# Thande.net
KiCad netlist of a schematic drawn in Altium Designer
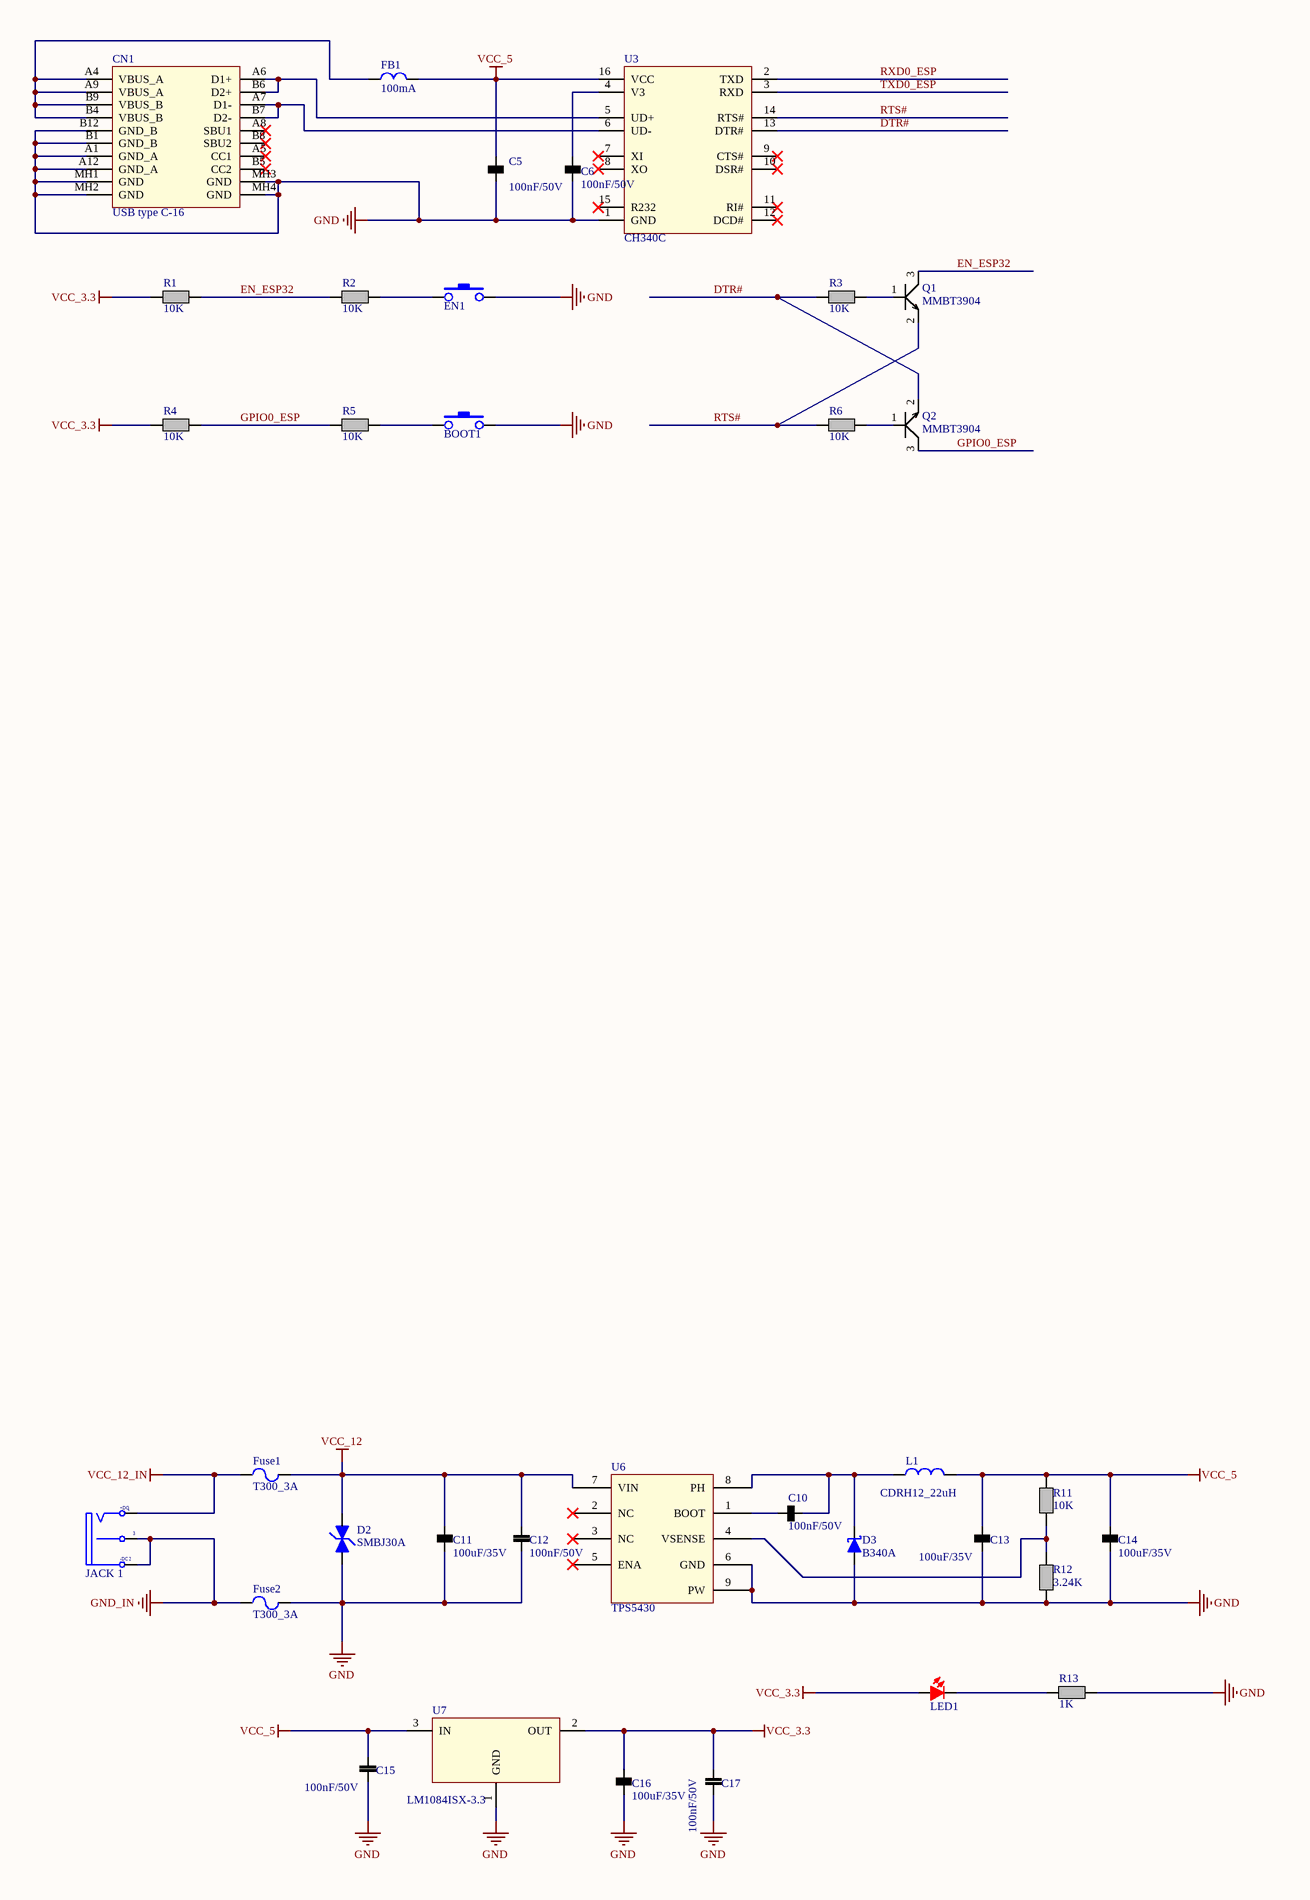
[diagram p0: Thande.SchDoc, left]
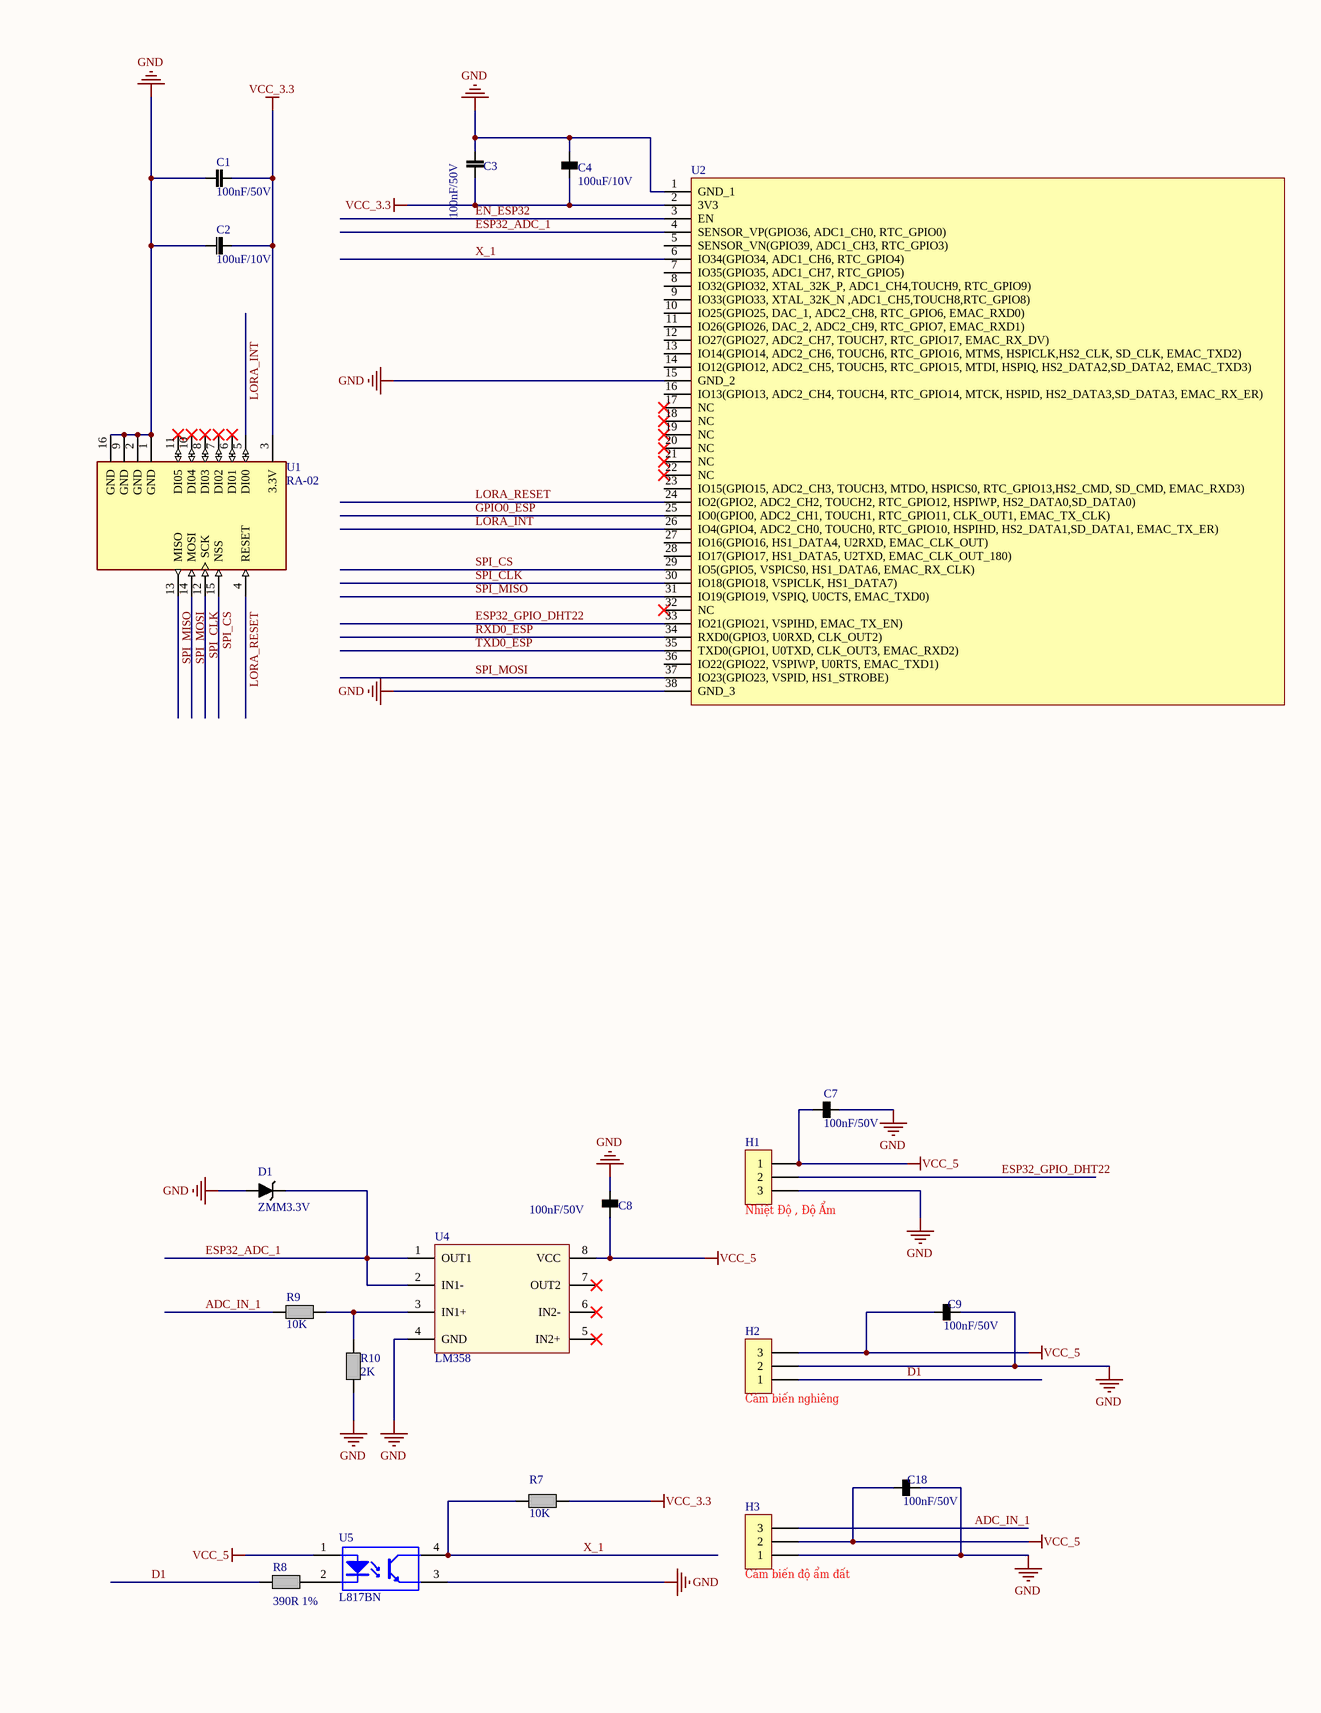
[diagram p1: Thande.SchDoc, right]

(export (version "E")
  (design (tool "Eeschema 10.0.6"))
  (components
    (comp (ref "BOOT1")
      (value "SW_2pin_SMD")
      (footprint "SW2-SMD**")
      (libsource (lib "Milky_Way") (part "SW_2pin_SMD"))
    )
    (comp (ref "C1")
      (value "100nF/50V")
      (footprint "CAP-0805**")
      (description "2Pin-SMD-0805 ,Ceramic X7R")
      (libsource (lib "Milky_Way") (part "Cap-100nF/50V_0805"))
    )
    (comp (ref "C2")
      (value "100uF/10V")
      (footprint "CAP-TANTA-3528**")
      (description "Cap-Tantalum  SMD3528 3.5mm x 2.8mm")
      (libsource (lib "Milky_Way") (part "Cap-Tanta_100uF/10V 3528"))
    )
    (comp (ref "C3")
      (value "100nF/50V")
      (footprint "CAP-0805**")
      (description "2Pin-SMD-0805 ,Ceramic X7R")
      (libsource (lib "Milky_Way") (part "Cap-100nF/50V_0805"))
    )
    (comp (ref "C4")
      (value "100uF/10V")
      (footprint "CAP-TANTA-3528**")
      (description "Cap-Tantalum  SMD3528 3.5mm x 2.8mm")
      (libsource (lib "") (part "Cap-Tanta_100uF/10V 3528_1"))
    )
    (comp (ref "C5")
      (value "100nF/50V")
      (footprint "CAP-0805**")
      (description "2Pin-SMD-0805 ,Ceramic X7R")
      (libsource (lib "Milky_Way") (part "Cap-100nF/50V_0805"))
    )
    (comp (ref "C6")
      (value "100nF/50V")
      (footprint "CAP-0805**")
      (description "2Pin-SMD-0805 ,Ceramic X7R")
      (libsource (lib "Milky_Way") (part "Cap-100nF/50V_0805"))
    )
    (comp (ref "C7")
      (value "100nF/50V")
      (footprint "CAP-0805**")
      (description "2Pin-SMD-0805 ,Ceramic X7R")
      (libsource (lib "Milky_Way") (part "Cap-100nF/50V_0805"))
    )
    (comp (ref "C8")
      (value "100nF/50V")
      (footprint "CAP-0805**")
      (description "2Pin-SMD-0805 ,Ceramic X7R")
      (libsource (lib "Milky_Way") (part "Cap-100nF/50V_0805"))
    )
    (comp (ref "C9")
      (value "100nF/50V")
      (footprint "CAP-0805**")
      (description "2Pin-SMD-0805 ,Ceramic X7R")
      (libsource (lib "Milky_Way") (part "Cap-100nF/50V_0805"))
    )
    (comp (ref "C10")
      (value "100nF/50V")
      (footprint "CAP-0805**")
      (description "2Pin-SMD-0805 ,Ceramic X7R")
      (libsource (lib "Milky_Way") (part "Cap-100nF/50V_0805"))
    )
    (comp (ref "C11")
      (value "100uF/35V")
      (footprint "CAP-AL- Size D8_6.3×7.7 mm**")
      (description "Cap-Al-Size D8_6.3×7.7 mm")
      (libsource (lib "Milky_Way") (part "Cap-Al_100uF/35V"))
    )
    (comp (ref "C12")
      (value "100nF/50V")
      (footprint "CAP-0805**")
      (description "2Pin-SMD-0805 ,Ceramic X7R")
      (libsource (lib "Milky_Way") (part "Cap-100nF/50V_0805"))
    )
    (comp (ref "C13")
      (value "100uF/35V")
      (footprint "CAP-AL- Size D8_6.3×7.7 mm**")
      (description "Cap-Al-Size D8_6.3×7.7 mm")
      (libsource (lib "Milky_Way") (part "Cap-Al_100uF/35V"))
    )
    (comp (ref "C14")
      (value "100uF/35V")
      (footprint "CAP-AL- Size D8_6.3×7.7 mm**")
      (description "Cap-Al-Size D8_6.3×7.7 mm")
      (libsource (lib "Milky_Way") (part "Cap-Al_100uF/35V"))
    )
    (comp (ref "C15")
      (value "100nF/50V")
      (footprint "CAP-0805**")
      (description "2Pin-SMD-0805 ,Ceramic X7R")
      (libsource (lib "Milky_Way") (part "Cap-100nF/50V_0805"))
    )
    (comp (ref "C16")
      (value "100uF/35V")
      (footprint "CAP-AL- Size D8_6.3×7.7 mm**")
      (description "Cap-Al-Size D8_6.3×7.7 mm")
      (libsource (lib "Milky_Way") (part "Cap-Al_100uF/35V"))
    )
    (comp (ref "C17")
      (value "100nF/50V")
      (footprint "CAP-0805**")
      (description "2Pin-SMD-0805 ,Ceramic X7R")
      (libsource (lib "Milky_Way") (part "Cap-100nF/50V_0805"))
    )
    (comp (ref "C18")
      (value "100nF/50V")
      (footprint "CAP-0805**")
      (description "2Pin-SMD-0805 ,Ceramic X7R")
      (libsource (lib "Milky_Way") (part "Cap-100nF/50V_0805"))
    )
    (comp (ref "CN1")
      (value "USB type C-16")
      (footprint "USB TYPE C-16**")
      (fields (field (name "MF") "Valcon") (field (name "MP") "CSP-USC16-TR"))
      (libsource (lib "Milky_Way") (part "USB type C-16"))
    )
    (comp (ref "D1")
      (value "ZMM3.3V")
      (footprint "DIO_SOD-80C**")
      (description "DZener_ZMM3.3V,SOD-80C")
      (libsource (lib "Milky_Way") (part "DZener_ZMM3.3V"))
    )
    (comp (ref "D2")
      (value "SMBJ30A")
      (footprint "DO-214AA**")
      (description "DO-214AA**")
      (libsource (lib "Milky_Way") (part "D-TVS_SMBJ30A"))
    )
    (comp (ref "D3")
      (value "B340A")
      (footprint "DO-214AC**")
      (description "DO_214AC")
      (fields (field (name "PUBLISHER") "Altium Limited"))
      (libsource (lib "Milky_Way") (part "DSchottky_B340A"))
    )
    (comp (ref "EN1")
      (value "SW_2pin_SMD")
      (footprint "SW2-SMD**")
      (libsource (lib "Milky_Way") (part "SW_2pin_SMD"))
    )
    (comp (ref "FB1")
      (value "100mA")
      (footprint "FB 0805**")
      (description "FB0805/600R/0805")
      (fields (field (name "PUBLISHER") "Altium Limited"))
      (libsource (lib "Milky_Way") (part "FB0805/600R_0805"))
    )
    (comp (ref "Fuse1")
      (value "T300_3A")
      (footprint "FUSE-1812**")
      (description "SMD 1812")
      (libsource (lib "Milky_Way") (part "FUSE 3A _1812"))
    )
    (comp (ref "Fuse2")
      (value "T300_3A")
      (footprint "FUSE-1812**")
      (description "SMD 1812")
      (libsource (lib "Milky_Way") (part "FUSE 3A _1812"))
    )
    (comp (ref "H1")
      (value "Header 3P 2.54 Duc Thang")
      (footprint "XH2.54M-3")
      (description "Cắm")
      (libsource (lib "") (part "Header 3P 2.54 Duc Thang_1"))
    )
    (comp (ref "H2")
      (value "Header 3P 2.54 Duc Thang")
      (footprint "XH2.54M-3")
      (description "Cắm")
      (libsource (lib "Altium_Lib_by_KhueNguyenCreator") (part "Header 3P 2.54 Duc Thang"))
    )
    (comp (ref "H3")
      (value "Header 3P 2.54 Duc Thang")
      (footprint "XH2.54M-3")
      (description "Cắm")
      (libsource (lib "Altium_Lib_by_KhueNguyenCreator") (part "Header 3P 2.54 Duc Thang"))
    )
    (comp (ref "JACK 1")
      (value "DC3501")
      (footprint "DC_005**")
      (description "Jack DC3.5x1.3MM DC3501")
      (libsource (lib "Milky_Way") (part "Jack  DC3501"))
    )
    (comp (ref "L1")
      (value "CDRH12_22uH")
      (footprint "IND_CDRH12_12x12x7MM**")
      (description "CDRH12_12x12x7MM**")
      (fields
        (field (name "MANUFACTURER") "Generic Components")
        (field (name "PUBLISHER") "Altium Hobart Technology Centre")
      )
      (libsource (lib "Milky_Way") (part "IN_CDRH12_22uH"))
    )
    (comp (ref "LED1")
      (value "LedRed")
      (footprint "LED-0805-Red**")
      (description "2Pin-SMD")
      (libsource (lib "Milky_Way") (part "LedRed"))
    )
    (comp (ref "Q1")
      (value "MMBT3904")
      (footprint "SOT23-3 **")
      (description "3PIN-SOT23,MMBT3904")
      (libsource (lib "Milky_Way") (part "TRA-N_MMBT3904"))
    )
    (comp (ref "Q2")
      (value "MMBT3904")
      (footprint "SOT23-3 **")
      (description "3PIN-SOT23,MMBT3904")
      (libsource (lib "Milky_Way") (part "TRA-N_MMBT3904"))
    )
    (comp (ref "R1")
      (value "10K")
      (footprint "Res-0805**")
      (description "Res-10K 0805 SMD")
      (libsource (lib "Milky_Way") (part "Res-10K 0805 SMD"))
    )
    (comp (ref "R2")
      (value "10K")
      (footprint "Res-0805**")
      (description "Res-10K 0805 SMD")
      (libsource (lib "Milky_Way") (part "Res-10K 0805 SMD"))
    )
    (comp (ref "R3")
      (value "10K")
      (footprint "Res-0805**")
      (description "Res-10K 0805 SMD")
      (libsource (lib "Milky_Way") (part "Res-10K 0805 SMD"))
    )
    (comp (ref "R4")
      (value "10K")
      (footprint "Res-0805**")
      (description "Res-10K 0805 SMD")
      (libsource (lib "Milky_Way") (part "Res-10K 0805 SMD"))
    )
    (comp (ref "R5")
      (value "10K")
      (footprint "Res-0805**")
      (description "Res-10K 0805 SMD")
      (libsource (lib "Milky_Way") (part "Res-10K 0805 SMD"))
    )
    (comp (ref "R6")
      (value "10K")
      (footprint "Res-0805**")
      (description "Res-10K 0805 SMD")
      (libsource (lib "Milky_Way") (part "Res-10K 0805 SMD"))
    )
    (comp (ref "R7")
      (value "10K")
      (footprint "Res-0805**")
      (description "Res-10K 0805 SMD")
      (libsource (lib "Milky_Way") (part "Res-10K 0805 SMD"))
    )
    (comp (ref "R8")
      (value "390R 1%")
      (footprint "Res-0805**")
      (libsource (lib "Milky_Way") (part "Res-390R 1% 0805 SMD"))
    )
    (comp (ref "R9")
      (value "10K")
      (footprint "Res-0805**")
      (description "Res-10K 0805 SMD")
      (libsource (lib "Milky_Way") (part "Res-10K 0805 SMD"))
    )
    (comp (ref "R10")
      (value "2K")
      (footprint "Res-0805**")
      (description "Res-2KK 0805 SMD")
      (libsource (lib "Milky_Way") (part "Res-2K 0805 SMD"))
    )
    (comp (ref "R11")
      (value "10K")
      (footprint "Res-0805**")
      (description "Res-10K 0805 SMD")
      (libsource (lib "Milky_Way") (part "Res-10K 0805 SMD"))
    )
    (comp (ref "R12")
      (value "3.24K")
      (footprint "Res-0805**")
      (description "Res-3.24K 0805 SMD")
      (libsource (lib "Milky_Way") (part "Res-3.24K 0805 SMD"))
    )
    (comp (ref "R13")
      (value "1K")
      (footprint "Res-0805**")
      (description "Res-1K 0805 SMD")
      (libsource (lib "Milky_Way") (part "Res-1K 0805 SMD"))
    )
    (comp (ref "U1")
      (value "RA-02")
      (footprint "RA-02")
      (fields (field (name "MF") "Ai-Thinker"))
      (libsource (lib "RA-02") (part "RA-02"))
    )
    (comp (ref "U2")
      (value "~")
      (footprint "ESP32WROOM32E8MB")
      (description "Integrated Circuit")
      (fields
        (field (name "MANUFACTURER_PART_NUMBER") "ESP32-WROOM-32E (8MB)")
        (field (name "MOUSER PART NUMBER") "356-ESP32WRM32E164PH")
      )
      (libsource (lib "ThuVienDoAn") (part "ESP32-WROOM-32E__8MB_"))
    )
    (comp (ref "U3")
      (value "CH340C")
      (footprint "SOIC-16**")
      (description "16Pin-SOIC")
      (libsource (lib "Milky_Way") (part "CH340C"))
    )
    (comp (ref "U4")
      (value "LM358")
      (footprint "SOIC8**")
      (description "SOIC8")
      (libsource (lib "Milky_Way") (part "LM358"))
    )
    (comp (ref "U5")
      (value "L817BN")
      (footprint "SOP-4**")
      (description "L817BN SOP4")
      (libsource (lib "Milky_Way") (part "OPTO_L817BN"))
    )
    (comp (ref "U6")
      (value "TPS5430")
      (footprint "SOIC8-PAD**")
      (description "SOIC8 pad-Height 1.7mm")
      (libsource (lib "Milky_Way") (part "TPS5430"))
    )
    (comp (ref "U7")
      (value "LM1084ISX-3.3")
      (footprint "TO-263/D2PAK")
      (description "TO263-3")
      (libsource (lib "Milky_Way") (part "LM1084ISX-3.3"))
    )
  )
  (nets
    (net (code "2") (name "/ADC_IN_1") (class "Default")
      (node (ref "H3") (pin "3") (pinfunction "3_3") (pintype "passive"))
      (node (ref "R9") (pin "2") (pinfunction "2_2") (pintype "passive"))
    )
    (net (code "3") (name "/D1") (class "Default")
      (node (ref "H2") (pin "1") (pinfunction "1_1") (pintype "passive"))
      (node (ref "R8") (pin "1") (pinfunction "1_1") (pintype "passive"))
    )
    (net (code "4") (name "/DTR#") (class "Default")
      (node (ref "Q2") (pin "2") (pinfunction "2_2") (pintype "passive"))
      (node (ref "R3") (pin "2") (pinfunction "2_2") (pintype "passive"))
      (node (ref "U3") (pin "13") (pinfunction "DTR#_13") (pintype "passive"))
    )
    (net (code "5") (name "/EN_ESP32") (class "Default")
      (node (ref "Q1") (pin "3") (pinfunction "3_3") (pintype "passive"))
      (node (ref "R1") (pin "1") (pinfunction "1_1") (pintype "passive"))
      (node (ref "R2") (pin "2") (pinfunction "2_2") (pintype "passive"))
      (node (ref "U2") (pin "3") (pinfunction "EN_3") (pintype "passive"))
    )
    (net (code "6") (name "/ESP32_ADC_1") (class "Default")
      (node (ref "D1") (pin "2") (pinfunction "K_2") (pintype "passive"))
      (node (ref "U2") (pin "4") (pinfunction "SENSOR_VP(GPIO36,_ADC1_CH0,_RTC_GPIO0)_4") (pintype "passive"))
      (node (ref "U4") (pin "1") (pinfunction "OUT1_1") (pintype "passive"))
      (node (ref "U4") (pin "2") (pinfunction "IN1-_2") (pintype "passive"))
    )
    (net (code "7") (name "/ESP32_GPIO_DHT22") (class "Default")
      (node (ref "H1") (pin "2") (pinfunction "2_2") (pintype "passive"))
      (node (ref "U2") (pin "33") (pinfunction "IO21(GPIO21,_VSPIHD,_EMAC_TX_EN)_33") (pintype "passive"))
    )
    (net (code "8") (name "/GPIO0_ESP") (class "Default")
      (node (ref "Q2") (pin "3") (pinfunction "3_3") (pintype "passive"))
      (node (ref "R4") (pin "1") (pinfunction "1_1") (pintype "passive"))
      (node (ref "R5") (pin "2") (pinfunction "2_2") (pintype "passive"))
      (node (ref "U2") (pin "25") (pinfunction "IO0(GPIO0,_ADC2_CH1,_TOUCH1,_RTC_GPIO11,_CLK_OUT1,_EMAC_TX_CLK)_25") (pintype "passive"))
    )
    (net (code "9") (name "/LORA_INT") (class "Default")
      (node (ref "U1") (pin "5") (pinfunction "DI00_5") (pintype "bidirectional"))
      (node (ref "U2") (pin "26") (pinfunction "IO4(GPIO4,_ADC2_CH0,_TOUCH0,_RTC_GPIO10,_HSPIHD,_HS2_DATA1,SD_DATA1,_EMAC_TX_ER)_26") (pintype "passive"))
    )
    (net (code "10") (name "/LORA_RESET") (class "Default")
      (node (ref "U1") (pin "4") (pinfunction "RESET_4") (pintype "input"))
      (node (ref "U2") (pin "24") (pinfunction "IO2(GPIO2,_ADC2_CH2,_TOUCH2,_RTC_GPIO12,_HSPIWP,_HS2_DATA0,SD_DATA0)_24") (pintype "passive"))
    )
    (net (code "11") (name "/RTS#") (class "Default")
      (node (ref "Q1") (pin "2") (pinfunction "2_2") (pintype "passive"))
      (node (ref "R6") (pin "2") (pinfunction "2_2") (pintype "passive"))
      (node (ref "U3") (pin "14") (pinfunction "RTS#_14") (pintype "passive"))
    )
    (net (code "12") (name "/RXD0_ESP") (class "Default")
      (node (ref "U2") (pin "34") (pinfunction "RXD0(GPIO3,_U0RXD,_CLK_OUT2)_34") (pintype "passive"))
      (node (ref "U3") (pin "2") (pinfunction "TXD_2") (pintype "passive"))
    )
    (net (code "13") (name "/SPI_CLK") (class "Default")
      (node (ref "U1") (pin "12") (pinfunction "SCK_12") (pintype "input"))
      (node (ref "U2") (pin "30") (pinfunction "IO18(GPIO18,_VSPICLK,_HS1_DATA7)_30") (pintype "passive"))
    )
    (net (code "14") (name "/SPI_CS") (class "Default")
      (node (ref "U1") (pin "15") (pinfunction "NSS_15") (pintype "input"))
      (node (ref "U2") (pin "29") (pinfunction "IO5(GPIO5,_VSPICS0,_HS1_DATA6,_EMAC_RX_CLK)_29") (pintype "passive"))
    )
    (net (code "15") (name "/SPI_MISO") (class "Default")
      (node (ref "U1") (pin "13") (pinfunction "MISO_13") (pintype "output"))
      (node (ref "U2") (pin "31") (pinfunction "IO19(GPIO19,_VSPIQ,_U0CTS,_EMAC_TXD0)_31") (pintype "passive"))
    )
    (net (code "16") (name "/SPI_MOSI") (class "Default")
      (node (ref "U1") (pin "14") (pinfunction "MOSI_14") (pintype "input"))
      (node (ref "U2") (pin "37") (pinfunction "IO23(GPIO23,_VSPID,_HS1_STROBE)_37") (pintype "passive"))
    )
    (net (code "17") (name "/TXD0_ESP") (class "Default")
      (node (ref "U2") (pin "35") (pinfunction "TXD0(GPIO1,_U0TXD,_CLK_OUT3,_EMAC_RXD2)_35") (pintype "passive"))
      (node (ref "U3") (pin "3") (pinfunction "RXD_3") (pintype "passive"))
    )
    (net (code "18") (name "/X_1") (class "Default")
      (node (ref "R7") (pin "2") (pinfunction "2_2") (pintype "passive"))
      (node (ref "U2") (pin "6") (pinfunction "IO34(GPIO34,_ADC1_CH6,_RTC_GPIO4)_6") (pintype "passive"))
      (node (ref "U5") (pin "4") (pinfunction "4_4") (pintype "passive"))
    )
    (net (code "19") (name "GND") (class "Default")
      (node (ref "BOOT1") (pin "2") (pinfunction "2_2") (pintype "passive"))
      (node (ref "C1") (pin "1") (pinfunction "1_1") (pintype "passive"))
      (node (ref "C11") (pin "2") (pinfunction "-_2") (pintype "passive"))
      (node (ref "C12") (pin "1") (pinfunction "1_1") (pintype "passive"))
      (node (ref "C13") (pin "2") (pinfunction "-_2") (pintype "passive"))
      (node (ref "C14") (pin "2") (pinfunction "-_2") (pintype "passive"))
      (node (ref "C15") (pin "1") (pinfunction "1_1") (pintype "passive"))
      (node (ref "C16") (pin "2") (pinfunction "-_2") (pintype "passive"))
      (node (ref "C17") (pin "1") (pinfunction "1_1") (pintype "passive"))
      (node (ref "C18") (pin "1") (pinfunction "1_1") (pintype "passive"))
      (node (ref "C2") (pin "2") (pinfunction "-_2") (pintype "passive"))
      (node (ref "C3") (pin "2") (pinfunction "2_2") (pintype "passive"))
      (node (ref "C4") (pin "2") (pinfunction "-_2") (pintype "passive"))
      (node (ref "C5") (pin "2") (pinfunction "2_2") (pintype "passive"))
      (node (ref "C6") (pin "2") (pinfunction "2_2") (pintype "passive"))
      (node (ref "C7") (pin "2") (pinfunction "2_2") (pintype "passive"))
      (node (ref "C8") (pin "2") (pinfunction "2_2") (pintype "passive"))
      (node (ref "C9") (pin "1") (pinfunction "1_1") (pintype "passive"))
      (node (ref "CN1") (pin "A1") (pinfunction "GND_A_A1") (pintype "power_in"))
      (node (ref "CN1") (pin "A12") (pinfunction "GND_A_A12") (pintype "power_in"))
      (node (ref "CN1") (pin "B1") (pinfunction "GND_B_B1") (pintype "power_in"))
      (node (ref "CN1") (pin "B12") (pinfunction "GND_B_B12") (pintype "power_in"))
      (node (ref "CN1") (pin "MH1") (pinfunction "GND_MH1") (pintype "power_in"))
      (node (ref "CN1") (pin "MH2") (pinfunction "GND_MH2") (pintype "power_in"))
      (node (ref "CN1") (pin "MH3") (pinfunction "GND_MH3") (pintype "power_in"))
      (node (ref "CN1") (pin "MH4") (pinfunction "GND_MH4") (pintype "power_in"))
      (node (ref "D1") (pin "1") (pinfunction "A_1") (pintype "passive"))
      (node (ref "D2") (pin "1") (pinfunction "A_1") (pintype "passive"))
      (node (ref "D3") (pin "1") (pinfunction "A_1") (pintype "passive"))
      (node (ref "EN1") (pin "2") (pinfunction "2_2") (pintype "passive"))
      (node (ref "Fuse2") (pin "2") (pinfunction "2_2") (pintype "passive"))
      (node (ref "H1") (pin "3") (pinfunction "3_3") (pintype "passive"))
      (node (ref "H2") (pin "2") (pinfunction "2_2") (pintype "passive"))
      (node (ref "H3") (pin "1") (pinfunction "1_1") (pintype "passive"))
      (node (ref "R10") (pin "1") (pinfunction "1_1") (pintype "passive"))
      (node (ref "R12") (pin "1") (pinfunction "1_1") (pintype "passive"))
      (node (ref "R13") (pin "1") (pinfunction "1_1") (pintype "passive"))
      (node (ref "U1") (pin "1") (pinfunction "GND_1") (pintype "power_in"))
      (node (ref "U1") (pin "16") (pinfunction "GND_16") (pintype "power_in"))
      (node (ref "U1") (pin "2") (pinfunction "GND_2") (pintype "power_in"))
      (node (ref "U1") (pin "9") (pinfunction "GND_9") (pintype "power_in"))
      (node (ref "U2") (pin "1") (pinfunction "GND_1_1") (pintype "passive"))
      (node (ref "U2") (pin "15") (pinfunction "GND_2_15") (pintype "passive"))
      (node (ref "U2") (pin "38") (pinfunction "GND_3_38") (pintype "passive"))
      (node (ref "U3") (pin "1") (pinfunction "GND_1") (pintype "passive"))
      (node (ref "U4") (pin "4") (pinfunction "GND_4") (pintype "passive"))
      (node (ref "U5") (pin "3") (pinfunction "3_3") (pintype "passive"))
      (node (ref "U6") (pin "6") (pinfunction "GND_6") (pintype "passive"))
      (node (ref "U6") (pin "9") (pinfunction "PW_9") (pintype "passive"))
      (node (ref "U7") (pin "1") (pinfunction "GND_1") (pintype "passive"))
    )
    (net (code "20") (name "GND_IN") (class "Default")
      (node (ref "Fuse2") (pin "1") (pinfunction "1_1") (pintype "passive"))
      (node (ref "JACK 1") (pin "2") (pinfunction "TN_2") (pintype "passive"))
      (node (ref "JACK 1") (pin "3") (pinfunction "S_3") (pintype "power_in"))
    )
    (net (code "21") (name "Net-(BOOT1-Pad1)") (class "Default")
      (node (ref "BOOT1") (pin "1") (pinfunction "1_1") (pintype "passive"))
      (node (ref "R5") (pin "1") (pinfunction "1_1") (pintype "passive"))
    )
    (net (code "22") (name "Net-(CN1-D1+)") (class "Default")
      (node (ref "CN1") (pin "A6") (pinfunction "D1+_A6") (pintype "passive"))
      (node (ref "CN1") (pin "B6") (pinfunction "D2+_B6") (pintype "passive"))
      (node (ref "U3") (pin "5") (pinfunction "UD+_5") (pintype "passive"))
    )
    (net (code "23") (name "Net-(CN1-D1-)") (class "Default")
      (node (ref "CN1") (pin "A7") (pinfunction "D1-_A7") (pintype "passive"))
      (node (ref "CN1") (pin "B7") (pinfunction "D2-_B7") (pintype "passive"))
      (node (ref "U3") (pin "6") (pinfunction "UD-_6") (pintype "passive"))
    )
    (net (code "24") (name "Net-(CN1-VBUS_A-PadA4)") (class "Default")
      (node (ref "CN1") (pin "A4") (pinfunction "VBUS_A_A4") (pintype "power_in"))
      (node (ref "CN1") (pin "A9") (pinfunction "VBUS_A_A9") (pintype "power_in"))
      (node (ref "CN1") (pin "B4") (pinfunction "VBUS_B_B4") (pintype "power_in"))
      (node (ref "CN1") (pin "B9") (pinfunction "VBUS_B_B9") (pintype "power_in"))
      (node (ref "FB1") (pin "1") (pinfunction "1_1") (pintype "passive"))
    )
    (net (code "25") (name "Net-(D3-K)") (class "Default")
      (node (ref "C10") (pin "2") (pinfunction "2_2") (pintype "passive"))
      (node (ref "D3") (pin "2") (pinfunction "K_2") (pintype "passive"))
      (node (ref "L1") (pin "1") (pinfunction "1_1") (pintype "passive"))
      (node (ref "U6") (pin "8") (pinfunction "PH_8") (pintype "passive"))
    )
    (net (code "26") (name "Net-(EN1-Pad1)") (class "Default")
      (node (ref "EN1") (pin "1") (pinfunction "1_1") (pintype "passive"))
      (node (ref "R2") (pin "1") (pinfunction "1_1") (pintype "passive"))
    )
    (net (code "27") (name "Net-(LED1-K)") (class "Default")
      (node (ref "LED1") (pin "2") (pinfunction "K_2") (pintype "passive"))
      (node (ref "R13") (pin "2") (pinfunction "2_2") (pintype "passive"))
    )
    (net (code "28") (name "Net-(Q1-Pad1)") (class "Default")
      (node (ref "Q1") (pin "1") (pinfunction "1_1") (pintype "passive"))
      (node (ref "R3") (pin "1") (pinfunction "1_1") (pintype "passive"))
    )
    (net (code "29") (name "Net-(Q2-Pad1)") (class "Default")
      (node (ref "Q2") (pin "1") (pinfunction "1_1") (pintype "passive"))
      (node (ref "R6") (pin "1") (pinfunction "1_1") (pintype "passive"))
    )
    (net (code "30") (name "Net-(R8-Pad2)") (class "Default")
      (node (ref "R8") (pin "2") (pinfunction "2_2") (pintype "passive"))
      (node (ref "U5") (pin "2") (pinfunction "2_2") (pintype "passive"))
    )
    (net (code "31") (name "Net-(U3-V3)") (class "Default")
      (node (ref "C6") (pin "1") (pinfunction "1_1") (pintype "passive"))
      (node (ref "U3") (pin "4") (pinfunction "V3_4") (pintype "passive"))
    )
    (net (code "32") (name "Net-(U4-IN1+)") (class "Default")
      (node (ref "R10") (pin "2") (pinfunction "2_2") (pintype "passive"))
      (node (ref "R9") (pin "1") (pinfunction "1_1") (pintype "passive"))
      (node (ref "U4") (pin "3") (pinfunction "IN1+_3") (pintype "passive"))
    )
    (net (code "33") (name "Net-(U6-BOOT)") (class "Default")
      (node (ref "C10") (pin "1") (pinfunction "1_1") (pintype "passive"))
      (node (ref "U6") (pin "1") (pinfunction "BOOT_1") (pintype "passive"))
    )
    (net (code "34") (name "Net-(U6-VSENSE)") (class "Default")
      (node (ref "R11") (pin "1") (pinfunction "1_1") (pintype "passive"))
      (node (ref "R12") (pin "2") (pinfunction "2_2") (pintype "passive"))
      (node (ref "U6") (pin "4") (pinfunction "VSENSE_4") (pintype "passive"))
    )
    (net (code "35") (name "VCC_3.3") (class "Default")
      (node (ref "C1") (pin "2") (pinfunction "2_2") (pintype "passive"))
      (node (ref "C16") (pin "1") (pinfunction "+_1") (pintype "passive"))
      (node (ref "C17") (pin "2") (pinfunction "2_2") (pintype "passive"))
      (node (ref "C2") (pin "1") (pinfunction "+_1") (pintype "passive"))
      (node (ref "C3") (pin "1") (pinfunction "1_1") (pintype "passive"))
      (node (ref "C4") (pin "1") (pinfunction "+_1") (pintype "passive"))
      (node (ref "LED1") (pin "1") (pinfunction "A_1") (pintype "passive"))
      (node (ref "R1") (pin "2") (pinfunction "2_2") (pintype "passive"))
      (node (ref "R4") (pin "2") (pinfunction "2_2") (pintype "passive"))
      (node (ref "R7") (pin "1") (pinfunction "1_1") (pintype "passive"))
      (node (ref "U1") (pin "3") (pinfunction "3.3V_3") (pintype "power_in"))
      (node (ref "U2") (pin "2") (pinfunction "3V3_2") (pintype "passive"))
      (node (ref "U7") (pin "2") (pinfunction "OUT_2") (pintype "passive"))
    )
    (net (code "36") (name "VCC_5") (class "Default")
      (node (ref "C13") (pin "1") (pinfunction "+_1") (pintype "passive"))
      (node (ref "C14") (pin "1") (pinfunction "+_1") (pintype "passive"))
      (node (ref "C15") (pin "2") (pinfunction "2_2") (pintype "passive"))
      (node (ref "C18") (pin "2") (pinfunction "2_2") (pintype "passive"))
      (node (ref "C5") (pin "1") (pinfunction "1_1") (pintype "passive"))
      (node (ref "C7") (pin "1") (pinfunction "1_1") (pintype "passive"))
      (node (ref "C8") (pin "1") (pinfunction "1_1") (pintype "passive"))
      (node (ref "C9") (pin "2") (pinfunction "2_2") (pintype "passive"))
      (node (ref "FB1") (pin "2") (pinfunction "2_2") (pintype "passive"))
      (node (ref "H1") (pin "1") (pinfunction "1_1") (pintype "passive"))
      (node (ref "H2") (pin "3") (pinfunction "3_3") (pintype "passive"))
      (node (ref "H3") (pin "2") (pinfunction "2_2") (pintype "passive"))
      (node (ref "L1") (pin "2") (pinfunction "2_2") (pintype "passive"))
      (node (ref "R11") (pin "2") (pinfunction "2_2") (pintype "passive"))
      (node (ref "U3") (pin "16") (pinfunction "VCC_16") (pintype "passive"))
      (node (ref "U4") (pin "8") (pinfunction "VCC_8") (pintype "passive"))
      (node (ref "U5") (pin "1") (pinfunction "1_1") (pintype "passive"))
      (node (ref "U7") (pin "3") (pinfunction "IN_3") (pintype "passive"))
    )
    (net (code "37") (name "VCC_12") (class "Default")
      (node (ref "C11") (pin "1") (pinfunction "+_1") (pintype "passive"))
      (node (ref "C12") (pin "2") (pinfunction "2_2") (pintype "passive"))
      (node (ref "D2") (pin "2") (pinfunction "A_2") (pintype "passive"))
      (node (ref "Fuse1") (pin "2") (pinfunction "2_2") (pintype "passive"))
      (node (ref "U6") (pin "7") (pinfunction "VIN_7") (pintype "passive"))
    )
    (net (code "38") (name "VCC_12_IN") (class "Default")
      (node (ref "Fuse1") (pin "1") (pinfunction "1_1") (pintype "passive"))
      (node (ref "JACK 1") (pin "1") (pinfunction "T_1") (pintype "passive"))
    )
    (net (code "39") (name "unconnected-(CN1-CC1-PadA5)") (class "Default")
      (node (ref "CN1") (pin "A5") (pinfunction "CC1_A5") (pintype "passive+no_connect"))
    )
    (net (code "40") (name "unconnected-(CN1-CC2-PadB5)") (class "Default")
      (node (ref "CN1") (pin "B5") (pinfunction "CC2_B5") (pintype "passive+no_connect"))
    )
    (net (code "41") (name "unconnected-(CN1-SBU1-PadA8)") (class "Default")
      (node (ref "CN1") (pin "A8") (pinfunction "SBU1_A8") (pintype "passive+no_connect"))
    )
    (net (code "42") (name "unconnected-(CN1-SBU2-PadB8)") (class "Default")
      (node (ref "CN1") (pin "B8") (pinfunction "SBU2_B8") (pintype "passive+no_connect"))
    )
    (net (code "43") (name "unconnected-(U1-DI01-Pad6)") (class "Default")
      (node (ref "U1") (pin "6") (pinfunction "DI01_6") (pintype "bidirectional+no_connect"))
    )
    (net (code "44") (name "unconnected-(U1-DI02-Pad7)") (class "Default")
      (node (ref "U1") (pin "7") (pinfunction "DI02_7") (pintype "bidirectional+no_connect"))
    )
    (net (code "45") (name "unconnected-(U1-DI03-Pad8)") (class "Default")
      (node (ref "U1") (pin "8") (pinfunction "DI03_8") (pintype "bidirectional+no_connect"))
    )
    (net (code "46") (name "unconnected-(U1-DI04-Pad10)") (class "Default")
      (node (ref "U1") (pin "10") (pinfunction "DI04_10") (pintype "bidirectional+no_connect"))
    )
    (net (code "47") (name "unconnected-(U1-DI05-Pad11)") (class "Default")
      (node (ref "U1") (pin "11") (pinfunction "DI05_11") (pintype "bidirectional+no_connect"))
    )
    (net (code "48") (name "unconnected-(U2-IO12(GPIO12,_ADC2_CH5,_TOUCH5,_RTC_GPIO15,_MTDI,_HSPIQ,_HS2_DATA2,SD_DATA2,_EMAC_TXD3)-Pad14)") (class "Default")
      (node (ref "U2") (pin "14") (pinfunction "IO12(GPIO12,_ADC2_CH5,_TOUCH5,_RTC_GPIO15,_MTDI,_HSPIQ,_HS2_DATA2,SD_DATA2,_EMAC_TXD3)_14") (pintype "passive"))
    )
    (net (code "49") (name "unconnected-(U2-IO13(GPIO13,_ADC2_CH4,_TOUCH4,_RTC_GPIO14,_MTCK,_HSPID,_HS2_DATA3,SD_DATA3,_EMAC_RX_ER)-Pad16)") (class "Default")
      (node (ref "U2") (pin "16") (pinfunction "IO13(GPIO13,_ADC2_CH4,_TOUCH4,_RTC_GPIO14,_MTCK,_HSPID,_HS2_DATA3,SD_DATA3,_EMAC_RX_ER)_16") (pintype "passive"))
    )
    (net (code "50") (name "unconnected-(U2-IO14(GPIO14,_ADC2_CH6,_TOUCH6,_RTC_GPIO16,_MTMS,_HSPICLK,HS2_CLK,_SD_CLK,_EMAC_TXD2)-Pad13)") (class "Default")
      (node (ref "U2") (pin "13") (pinfunction "IO14(GPIO14,_ADC2_CH6,_TOUCH6,_RTC_GPIO16,_MTMS,_HSPICLK,HS2_CLK,_SD_CLK,_EMAC_TXD2)_13") (pintype "passive"))
    )
    (net (code "51") (name "unconnected-(U2-IO15(GPIO15,_ADC2_CH3,_TOUCH3,_MTDO,_HSPICS0,_RTC_GPIO13,HS2_CMD,_SD_CMD,_EMAC_RXD3)-Pad23)") (class "Default")
      (node (ref "U2") (pin "23") (pinfunction "IO15(GPIO15,_ADC2_CH3,_TOUCH3,_MTDO,_HSPICS0,_RTC_GPIO13,HS2_CMD,_SD_CMD,_EMAC_RXD3)_23") (pintype "passive"))
    )
    (net (code "52") (name "unconnected-(U2-IO16(GPIO16,_HS1_DATA4,_U2RXD,_EMAC_CLK_OUT)-Pad27)") (class "Default")
      (node (ref "U2") (pin "27") (pinfunction "IO16(GPIO16,_HS1_DATA4,_U2RXD,_EMAC_CLK_OUT)_27") (pintype "passive"))
    )
    (net (code "53") (name "unconnected-(U2-IO17(GPIO17,_HS1_DATA5,_U2TXD,_EMAC_CLK_OUT_180)-Pad28)") (class "Default")
      (node (ref "U2") (pin "28") (pinfunction "IO17(GPIO17,_HS1_DATA5,_U2TXD,_EMAC_CLK_OUT_180)_28") (pintype "passive"))
    )
    (net (code "54") (name "unconnected-(U2-IO22(GPIO22,_VSPIWP,_U0RTS,_EMAC_TXD1)-Pad36)") (class "Default")
      (node (ref "U2") (pin "36") (pinfunction "IO22(GPIO22,_VSPIWP,_U0RTS,_EMAC_TXD1)_36") (pintype "passive"))
    )
    (net (code "55") (name "unconnected-(U2-IO25(GPIO25,_DAC_1,_ADC2_CH8,_RTC_GPIO6,_EMAC_RXD0)-Pad10)") (class "Default")
      (node (ref "U2") (pin "10") (pinfunction "IO25(GPIO25,_DAC_1,_ADC2_CH8,_RTC_GPIO6,_EMAC_RXD0)_10") (pintype "passive"))
    )
    (net (code "56") (name "unconnected-(U2-IO26(GPIO26,_DAC_2,_ADC2_CH9,_RTC_GPIO7,_EMAC_RXD1)-Pad11)") (class "Default")
      (node (ref "U2") (pin "11") (pinfunction "IO26(GPIO26,_DAC_2,_ADC2_CH9,_RTC_GPIO7,_EMAC_RXD1)_11") (pintype "passive"))
    )
    (net (code "57") (name "unconnected-(U2-IO27(GPIO27,_ADC2_CH7,_TOUCH7,_RTC_GPIO17,_EMAC_RX_DV)-Pad12)") (class "Default")
      (node (ref "U2") (pin "12") (pinfunction "IO27(GPIO27,_ADC2_CH7,_TOUCH7,_RTC_GPIO17,_EMAC_RX_DV)_12") (pintype "passive"))
    )
    (net (code "58") (name "unconnected-(U2-IO32(GPIO32,_XTAL_32K_P,_ADC1_CH4,TOUCH9,_RTC_GPIO9)-Pad8)") (class "Default")
      (node (ref "U2") (pin "8") (pinfunction "IO32(GPIO32,_XTAL_32K_P,_ADC1_CH4,TOUCH9,_RTC_GPIO9)_8") (pintype "passive"))
    )
    (net (code "59") (name "unconnected-(U2-IO33(GPIO33,_XTAL_32K_N_,ADC1_CH5,TOUCH8,RTC_GPIO8)-Pad9)") (class "Default")
      (node (ref "U2") (pin "9") (pinfunction "IO33(GPIO33,_XTAL_32K_N_,ADC1_CH5,TOUCH8,RTC_GPIO8)_9") (pintype "passive"))
    )
    (net (code "60") (name "unconnected-(U2-IO35(GPIO35,_ADC1_CH7,_RTC_GPIO5)-Pad7)") (class "Default")
      (node (ref "U2") (pin "7") (pinfunction "IO35(GPIO35,_ADC1_CH7,_RTC_GPIO5)_7") (pintype "passive"))
    )
    (net (code "61") (name "unconnected-(U2-NC-Pad17)") (class "Default")
      (node (ref "U2") (pin "17") (pinfunction "NC_17") (pintype "passive+no_connect"))
    )
    (net (code "62") (name "unconnected-(U2-NC-Pad18)") (class "Default")
      (node (ref "U2") (pin "18") (pinfunction "NC_18") (pintype "passive+no_connect"))
    )
    (net (code "63") (name "unconnected-(U2-NC-Pad19)") (class "Default")
      (node (ref "U2") (pin "19") (pinfunction "NC_19") (pintype "passive+no_connect"))
    )
    (net (code "64") (name "unconnected-(U2-NC-Pad20)") (class "Default")
      (node (ref "U2") (pin "20") (pinfunction "NC_20") (pintype "passive+no_connect"))
    )
    (net (code "65") (name "unconnected-(U2-NC-Pad21)") (class "Default")
      (node (ref "U2") (pin "21") (pinfunction "NC_21") (pintype "passive+no_connect"))
    )
    (net (code "66") (name "unconnected-(U2-NC-Pad22)") (class "Default")
      (node (ref "U2") (pin "22") (pinfunction "NC_22") (pintype "passive+no_connect"))
    )
    (net (code "67") (name "unconnected-(U2-NC-Pad32)") (class "Default")
      (node (ref "U2") (pin "32") (pinfunction "NC_32") (pintype "passive+no_connect"))
    )
    (net (code "68") (name "unconnected-(U2-SENSOR_VN(GPIO39,_ADC1_CH3,_RTC_GPIO3)-Pad5)") (class "Default")
      (node (ref "U2") (pin "5") (pinfunction "SENSOR_VN(GPIO39,_ADC1_CH3,_RTC_GPIO3)_5") (pintype "passive"))
    )
    (net (code "69") (name "unconnected-(U3-CTS#-Pad9)") (class "Default")
      (node (ref "U3") (pin "9") (pinfunction "CTS#_9") (pintype "passive+no_connect"))
    )
    (net (code "70") (name "unconnected-(U3-DCD#-Pad12)") (class "Default")
      (node (ref "U3") (pin "12") (pinfunction "DCD#_12") (pintype "passive+no_connect"))
    )
    (net (code "71") (name "unconnected-(U3-DSR#-Pad10)") (class "Default")
      (node (ref "U3") (pin "10") (pinfunction "DSR#_10") (pintype "passive+no_connect"))
    )
    (net (code "72") (name "unconnected-(U3-R232-Pad15)") (class "Default")
      (node (ref "U3") (pin "15") (pinfunction "R232_15") (pintype "passive+no_connect"))
    )
    (net (code "73") (name "unconnected-(U3-RI#-Pad11)") (class "Default")
      (node (ref "U3") (pin "11") (pinfunction "RI#_11") (pintype "passive+no_connect"))
    )
    (net (code "74") (name "unconnected-(U3-XI-Pad7)") (class "Default")
      (node (ref "U3") (pin "7") (pinfunction "XI_7") (pintype "passive+no_connect"))
    )
    (net (code "75") (name "unconnected-(U3-XO-Pad8)") (class "Default")
      (node (ref "U3") (pin "8") (pinfunction "XO_8") (pintype "passive+no_connect"))
    )
    (net (code "76") (name "unconnected-(U4-IN2+-Pad5)") (class "Default")
      (node (ref "U4") (pin "5") (pinfunction "IN2+_5") (pintype "passive+no_connect"))
    )
    (net (code "77") (name "unconnected-(U4-IN2--Pad6)") (class "Default")
      (node (ref "U4") (pin "6") (pinfunction "IN2-_6") (pintype "passive+no_connect"))
    )
    (net (code "78") (name "unconnected-(U4-OUT2-Pad7)") (class "Default")
      (node (ref "U4") (pin "7") (pinfunction "OUT2_7") (pintype "passive+no_connect"))
    )
    (net (code "79") (name "unconnected-(U6-ENA-Pad5)") (class "Default")
      (node (ref "U6") (pin "5") (pinfunction "ENA_5") (pintype "passive+no_connect"))
    )
    (net (code "80") (name "unconnected-(U6-NC-Pad2)") (class "Default")
      (node (ref "U6") (pin "2") (pinfunction "NC_2") (pintype "passive+no_connect"))
    )
    (net (code "81") (name "unconnected-(U6-NC-Pad3)") (class "Default")
      (node (ref "U6") (pin "3") (pinfunction "NC_3") (pintype "passive+no_connect"))
    )
  )
)
